# design.net
KiCad netlist of a schematic drawn in Altium Designer
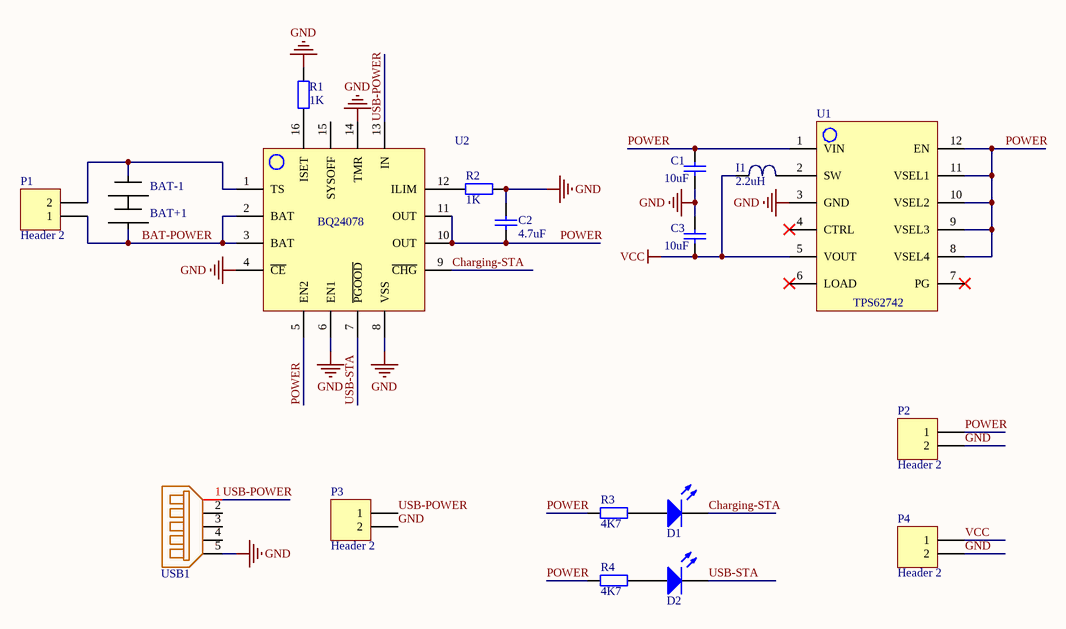
[diagram p0: 电池模块_原理图.SchDoc]

(export (version "E")
  (design (tool "Eeschema 10.0.6"))
  (components
    (comp (ref "BAT+1") (value "BAT") (footprint "BAT+") (libsource (lib "原理图库") (part "BAT")))
    (comp (ref "BAT-1") (value "BAT") (footprint "BTA-") (libsource (lib "原理图库") (part "BAT")))
    (comp (ref "C1")
      (value "10uF")
      (footprint "1__0603-CAP_")
      (description "Capacitor")
      (libsource (lib "Miscellaneous Devices") (part "Cap"))
    )
    (comp (ref "C2")
      (value "4.7uF")
      (footprint "1__0603-CAP_")
      (description "Capacitor")
      (libsource (lib "Miscellaneous Devices") (part "Cap"))
    )
    (comp (ref "C3")
      (value "10uF")
      (footprint "1__0603-CAP_")
      (description "Capacitor")
      (libsource (lib "Miscellaneous Devices") (part "Cap"))
    )
    (comp (ref "D1")
      (value "LED")
      (footprint "1__0603-LED_")
      (description "Typical INFRARED GaAs LED")
      (libsource (lib "Miscellaneous Devices") (part "LED0"))
    )
    (comp (ref "D2")
      (value "LED")
      (footprint "1__0603-LED_")
      (description "Typical INFRARED GaAs LED")
      (libsource (lib "Miscellaneous Devices") (part "LED0"))
    )
    (comp (ref "I1") (value "2.2uH") (footprint "1__0805_IND") (libsource (lib "常用原理图_by_K") (part "电感")))
    (comp (ref "P1")
      (value "Header 2")
      (footprint "HDR1X2")
      (description "Header, 2-Pin")
      (fields (field (name "PUBLISHER") "Altium Limited"))
      (libsource (lib "") (part "Header 2_1"))
    )
    (comp (ref "P2")
      (value "Header 2")
      (footprint "HDR1X2")
      (description "Header, 2-Pin")
      (fields (field (name "PUBLISHER") "Altium Limited"))
      (libsource (lib "!)Miscellaneous Integrated Library") (part "Header 2"))
    )
    (comp (ref "P3")
      (value "Header 2")
      (footprint "HDR1X2")
      (description "Header, 2-Pin")
      (fields (field (name "PUBLISHER") "Altium Limited"))
      (libsource (lib "!)Miscellaneous Integrated Library") (part "Header 2"))
    )
    (comp (ref "P4")
      (value "Header 2")
      (footprint "HDR1X2")
      (description "Header, 2-Pin")
      (fields (field (name "PUBLISHER") "Altium Limited"))
      (libsource (lib "!)Miscellaneous Integrated Library") (part "Header 2"))
    )
    (comp (ref "R1")
      (value "1K")
      (footprint "1__0603-RES_")
      (description "Resistor")
      (libsource (lib "Miscellaneous Devices") (part "Res2"))
    )
    (comp (ref "R2")
      (value "1K")
      (footprint "1__0603-RES_")
      (description "Resistor")
      (libsource (lib "") (part "Res2_2"))
    )
    (comp (ref "R3")
      (value "4K7")
      (footprint "1__0603-RES_")
      (description "Resistor")
      (libsource (lib "") (part "Res2_1"))
    )
    (comp (ref "R4")
      (value "4K7")
      (footprint "1__0603-RES_")
      (description "Resistor")
      (libsource (lib "") (part "Res2_1"))
    )
    (comp (ref "U1")
      (value "TPS62742")
      (footprint "TPS62742")
      (description "锂电池稳压")
      (libsource (lib "原理图库") (part "TPS62742"))
    )
    (comp (ref "U2")
      (value "BQ24078")
      (footprint "BQ24078")
      (description "充电芯片")
      (libsource (lib "原理图库") (part "BQ24078"))
    )
    (comp (ref "USB1")
      (value "USB-5P")
      (footprint "1__Micro USB 立贴_")
      (description "USB CONNECTOR")
      (libsource (lib "!)Miscellaneous Integrated Library") (part "USB-5P"))
    )
  )
  (nets
    (net (code "1") (name "/BAT-POWER") (class "Default")
      (node (ref "BAT+1") (pin "1") (pintype "passive"))
      (node (ref "P1") (pin "1") (pinfunction "1_1") (pintype "passive"))
      (node (ref "U2") (pin "2") (pinfunction "BAT_2") (pintype "passive"))
      (node (ref "U2") (pin "3") (pinfunction "BAT_3") (pintype "passive"))
    )
    (net (code "2") (name "/Charging-STA") (class "Default")
      (node (ref "D1") (pin "2") (pinfunction "2_2") (pintype "passive"))
      (node (ref "U2") (pin "9") (pinfunction "~{CHG}_9") (pintype "passive"))
    )
    (net (code "3") (name "/POWER") (class "Default")
      (node (ref "C1") (pin "2") (pinfunction "2_2") (pintype "passive"))
      (node (ref "C2") (pin "1") (pinfunction "1_1") (pintype "passive"))
      (node (ref "P2") (pin "1") (pinfunction "1_1") (pintype "passive"))
      (node (ref "R3") (pin "1") (pinfunction "1_1") (pintype "passive"))
      (node (ref "R4") (pin "1") (pinfunction "1_1") (pintype "passive"))
      (node (ref "U1") (pin "1") (pinfunction "VIN_1") (pintype "passive"))
      (node (ref "U1") (pin "10") (pinfunction "VSEL2_10") (pintype "passive"))
      (node (ref "U1") (pin "11") (pinfunction "VSEL1_11") (pintype "passive"))
      (node (ref "U1") (pin "12") (pinfunction "EN_12") (pintype "passive"))
      (node (ref "U1") (pin "8") (pinfunction "VSEL4_8") (pintype "passive"))
      (node (ref "U1") (pin "9") (pinfunction "VSEL3_9") (pintype "passive"))
      (node (ref "U2") (pin "10") (pinfunction "OUT_10") (pintype "passive"))
      (node (ref "U2") (pin "11") (pinfunction "OUT_11") (pintype "passive"))
      (node (ref "U2") (pin "5") (pinfunction "EN2_5") (pintype "passive"))
    )
    (net (code "4") (name "/USB-POWER") (class "Default")
      (node (ref "P3") (pin "1") (pinfunction "1_1") (pintype "passive"))
      (node (ref "U2") (pin "13") (pinfunction "IN_13") (pintype "passive"))
      (node (ref "USB1") (pin "1") (pinfunction "VBUS_1") (pintype "passive"))
    )
    (net (code "5") (name "/USB-STA") (class "Default")
      (node (ref "D2") (pin "2") (pinfunction "2_2") (pintype "passive"))
      (node (ref "U2") (pin "7") (pinfunction "~{PGOOD}_7") (pintype "passive"))
    )
    (net (code "6") (name "GND") (class "Default")
      (node (ref "C1") (pin "1") (pinfunction "1_1") (pintype "passive"))
      (node (ref "C2") (pin "2") (pinfunction "2_2") (pintype "passive"))
      (node (ref "C3") (pin "2") (pinfunction "2_2") (pintype "passive"))
      (node (ref "P2") (pin "2") (pinfunction "2_2") (pintype "passive"))
      (node (ref "P3") (pin "2") (pinfunction "2_2") (pintype "passive"))
      (node (ref "P4") (pin "2") (pinfunction "2_2") (pintype "passive"))
      (node (ref "R1") (pin "1") (pinfunction "1_1") (pintype "passive"))
      (node (ref "R2") (pin "1") (pinfunction "1_1") (pintype "passive"))
      (node (ref "U1") (pin "3") (pinfunction "GND_3") (pintype "passive"))
      (node (ref "U2") (pin "14") (pinfunction "TMR_14") (pintype "passive"))
      (node (ref "U2") (pin "4") (pinfunction "~{CE}_4") (pintype "passive"))
      (node (ref "U2") (pin "6") (pinfunction "EN1_6") (pintype "passive"))
      (node (ref "U2") (pin "8") (pinfunction "VSS_8") (pintype "passive"))
      (node (ref "USB1") (pin "5") (pinfunction "GND_5") (pintype "passive"))
    )
    (net (code "7") (name "Net-(BAT+1-Pad2)") (class "Default")
      (node (ref "BAT+1") (pin "2") (pintype "passive"))
      (node (ref "BAT-1") (pin "1") (pintype "passive"))
    )
    (net (code "8") (name "Net-(D1-Pad1)") (class "Default")
      (node (ref "D1") (pin "1") (pinfunction "1_1") (pintype "passive"))
      (node (ref "R3") (pin "2") (pinfunction "2_2") (pintype "passive"))
    )
    (net (code "9") (name "Net-(D2-Pad1)") (class "Default")
      (node (ref "D2") (pin "1") (pinfunction "1_1") (pintype "passive"))
      (node (ref "R4") (pin "2") (pinfunction "2_2") (pintype "passive"))
    )
    (net (code "10") (name "Net-(U1-SW)") (class "Default")
      (node (ref "I1") (pin "2") (pinfunction "2_2") (pintype "passive"))
      (node (ref "U1") (pin "2") (pinfunction "SW_2") (pintype "passive"))
    )
    (net (code "11") (name "Net-(U2-ILIM)") (class "Default")
      (node (ref "R2") (pin "2") (pinfunction "2_2") (pintype "passive"))
      (node (ref "U2") (pin "12") (pinfunction "ILIM_12") (pintype "passive"))
    )
    (net (code "12") (name "Net-(U2-ISET)") (class "Default")
      (node (ref "R1") (pin "2") (pinfunction "2_2") (pintype "passive"))
      (node (ref "U2") (pin "16") (pinfunction "ISET_16") (pintype "passive"))
    )
    (net (code "13") (name "Net-(U2-TS)") (class "Default")
      (node (ref "BAT-1") (pin "2") (pintype "passive"))
      (node (ref "P1") (pin "2") (pinfunction "2_2") (pintype "passive"))
      (node (ref "U2") (pin "1") (pinfunction "TS_1") (pintype "passive"))
    )
    (net (code "14") (name "VCC") (class "Default")
      (node (ref "C3") (pin "1") (pinfunction "1_1") (pintype "passive"))
      (node (ref "I1") (pin "1") (pinfunction "1_1") (pintype "passive"))
      (node (ref "P4") (pin "1") (pinfunction "1_1") (pintype "passive"))
      (node (ref "U1") (pin "5") (pinfunction "VOUT_5") (pintype "passive"))
    )
    (net (code "15") (name "unconnected-(U1-CTRL-Pad4)") (class "Default")
      (node (ref "U1") (pin "4") (pinfunction "CTRL_4") (pintype "passive+no_connect"))
    )
    (net (code "16") (name "unconnected-(U1-LOAD-Pad6)") (class "Default")
      (node (ref "U1") (pin "6") (pinfunction "LOAD_6") (pintype "passive+no_connect"))
    )
    (net (code "17") (name "unconnected-(U1-PG-Pad7)") (class "Default")
      (node (ref "U1") (pin "7") (pinfunction "PG_7") (pintype "passive+no_connect"))
    )
    (net (code "18") (name "unconnected-(U2-SYSOFF-Pad15)") (class "Default")
      (node (ref "U2") (pin "15") (pinfunction "SYSOFF_15") (pintype "passive"))
    )
    (net (code "19") (name "unconnected-(USB1-D+-Pad3)") (class "Default")
      (node (ref "USB1") (pin "3") (pinfunction "D+_3") (pintype "passive"))
    )
    (net (code "20") (name "unconnected-(USB1-D--Pad2)") (class "Default")
      (node (ref "USB1") (pin "2") (pinfunction "D-_2") (pintype "passive"))
    )
    (net (code "21") (name "unconnected-(USB1-ID-Pad4)") (class "Default")
      (node (ref "USB1") (pin "4") (pinfunction "ID_4") (pintype "passive"))
    )
  )
)
